# RS232.net
KiCad netlist of a schematic drawn in Altium Designer
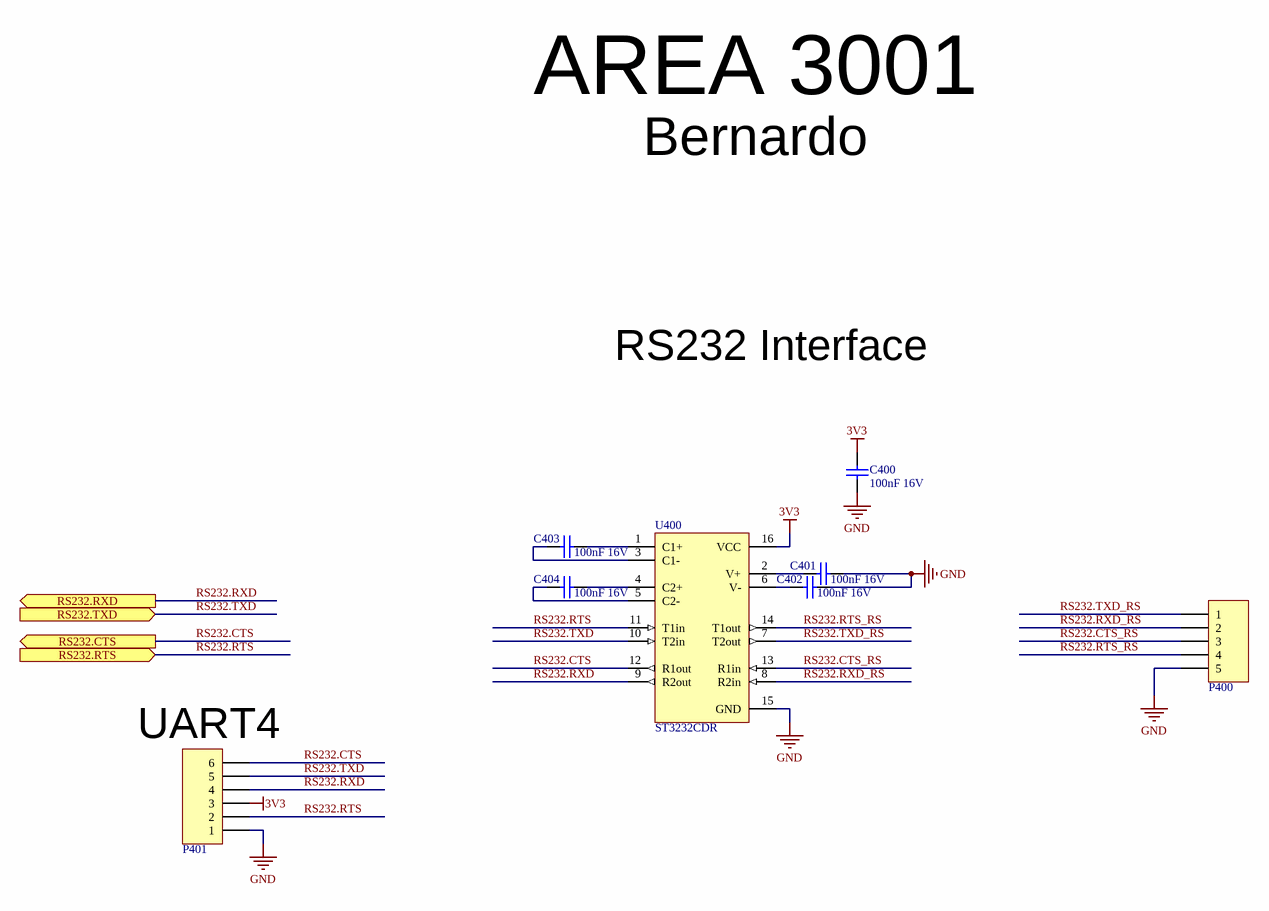
[diagram p0: RS232.SchDoc]

(export (version "E")
  (design (tool "Eeschema 10.0.6"))
  (components
    (comp (ref "C400")
      (value "100nF 16V")
      (footprint "C0603_N")
      (description "Capacitor Ceramic")
      (fields (field (name "Comment") "CAP_CERAMIC"))
      (libsource (lib "Phyx_Components") (part "CAP_CERAMIC"))
    )
    (comp (ref "C401")
      (value "100nF 16V")
      (footprint "C0603_N")
      (description "Capacitor Ceramic")
      (fields (field (name "Comment") "CAP_CERAMIC"))
      (libsource (lib "Phyx_Components") (part "CAP_CERAMIC"))
    )
    (comp (ref "C402")
      (value "100nF 16V")
      (footprint "C0603_N")
      (description "Capacitor Ceramic")
      (fields (field (name "Comment") "CAP_CERAMIC"))
      (libsource (lib "Phyx_Components") (part "CAP_CERAMIC"))
    )
    (comp (ref "C403")
      (value "100nF 16V")
      (footprint "C0603_N")
      (description "Capacitor Ceramic")
      (fields (field (name "Comment") "CAP_CERAMIC"))
      (libsource (lib "Phyx_Components") (part "CAP_CERAMIC"))
    )
    (comp (ref "C404")
      (value "100nF 16V")
      (footprint "C0603_N")
      (description "Capacitor Ceramic")
      (fields (field (name "Comment") "CAP_CERAMIC"))
      (libsource (lib "Phyx_Components") (part "CAP_CERAMIC"))
    )
    (comp (ref "P400")
      (value "5 Terminal Socket 2,5mm")
      (footprint "WE_691382000005")
      (libsource (lib "Phyx_Components") (part "Header 5"))
    )
    (comp (ref "P401")
      (value "Header 6")
      (footprint "HDR1X6")
      (libsource (lib "Phyx_Components") (part "Header 6"))
    )
    (comp (ref "U400")
      (value "ST3232CDR")
      (footprint "SOIC_N_16")
      (description "=Description")
      (fields (field (name "Comment") "RS-232 3V3 Transceiver SOIC"))
      (libsource (lib "Phyx_Components") (part "STM_ST3232"))
    )
  )
  (nets
    (net (code "1") (name "/RS232.CTS") (class "Default")
      (node (ref "P401") (pin "6") (pinfunction "6_6") (pintype "passive"))
      (node (ref "U400") (pin "12") (pinfunction "R1out_12") (pintype "output"))
    )
    (net (code "2") (name "/RS232.CTS_RS") (class "Default")
      (node (ref "P400") (pin "3") (pinfunction "3_3") (pintype "passive"))
      (node (ref "U400") (pin "13") (pinfunction "R1in_13") (pintype "input"))
    )
    (net (code "3") (name "/RS232.RTS") (class "Default")
      (node (ref "P401") (pin "2") (pinfunction "2_2") (pintype "passive"))
      (node (ref "U400") (pin "11") (pinfunction "T1in_11") (pintype "input"))
    )
    (net (code "4") (name "/RS232.RTS_RS") (class "Default")
      (node (ref "P400") (pin "4") (pinfunction "4_4") (pintype "passive"))
      (node (ref "U400") (pin "14") (pinfunction "T1out_14") (pintype "output"))
    )
    (net (code "5") (name "/RS232.RXD") (class "Default")
      (node (ref "P401") (pin "4") (pinfunction "4_4") (pintype "passive"))
      (node (ref "U400") (pin "9") (pinfunction "R2out_9") (pintype "output"))
    )
    (net (code "6") (name "/RS232.RXD_RS") (class "Default")
      (node (ref "P400") (pin "2") (pinfunction "2_2") (pintype "passive"))
      (node (ref "U400") (pin "8") (pinfunction "R2in_8") (pintype "input"))
    )
    (net (code "7") (name "/RS232.TXD") (class "Default")
      (node (ref "P401") (pin "5") (pinfunction "5_5") (pintype "passive"))
      (node (ref "U400") (pin "10") (pinfunction "T2in_10") (pintype "input"))
    )
    (net (code "8") (name "/RS232.TXD_RS") (class "Default")
      (node (ref "P400") (pin "1") (pinfunction "1_1") (pintype "passive"))
      (node (ref "U400") (pin "7") (pinfunction "T2out_7") (pintype "output"))
    )
    (net (code "9") (name "3V3") (class "Default")
      (node (ref "C400") (pin "1") (pinfunction "1_1") (pintype "passive"))
      (node (ref "P401") (pin "3") (pinfunction "3_3") (pintype "passive"))
      (node (ref "U400") (pin "16") (pinfunction "VCC_16") (pintype "power_in"))
    )
    (net (code "10") (name "GND") (class "Default")
      (node (ref "C400") (pin "2") (pinfunction "2_2") (pintype "passive"))
      (node (ref "C401") (pin "2") (pinfunction "2_2") (pintype "passive"))
      (node (ref "C402") (pin "2") (pinfunction "2_2") (pintype "passive"))
      (node (ref "P400") (pin "5") (pinfunction "5_5") (pintype "passive"))
      (node (ref "P401") (pin "1") (pinfunction "1_1") (pintype "passive"))
      (node (ref "U400") (pin "15") (pinfunction "GND_15") (pintype "power_in"))
    )
    (net (code "11") (name "Net-(U400-C1+)") (class "Default")
      (node (ref "C403") (pin "2") (pinfunction "2_2") (pintype "passive"))
      (node (ref "U400") (pin "1") (pinfunction "C1+_1") (pintype "passive"))
    )
    (net (code "12") (name "Net-(U400-C1-)") (class "Default")
      (node (ref "C403") (pin "1") (pinfunction "1_1") (pintype "passive"))
      (node (ref "U400") (pin "3") (pinfunction "C1-_3") (pintype "passive"))
    )
    (net (code "13") (name "Net-(U400-C2+)") (class "Default")
      (node (ref "C404") (pin "2") (pinfunction "2_2") (pintype "passive"))
      (node (ref "U400") (pin "4") (pinfunction "C2+_4") (pintype "passive"))
    )
    (net (code "14") (name "Net-(U400-C2-)") (class "Default")
      (node (ref "C404") (pin "1") (pinfunction "1_1") (pintype "passive"))
      (node (ref "U400") (pin "5") (pinfunction "C2-_5") (pintype "passive"))
    )
    (net (code "15") (name "Net-(U400-V+)") (class "Default")
      (node (ref "C401") (pin "1") (pinfunction "1_1") (pintype "passive"))
      (node (ref "U400") (pin "2") (pinfunction "V+_2") (pintype "passive"))
    )
    (net (code "16") (name "Net-(U400-V-)") (class "Default")
      (node (ref "C402") (pin "1") (pinfunction "1_1") (pintype "passive"))
      (node (ref "U400") (pin "6") (pinfunction "V-_6") (pintype "passive"))
    )
  )
)
